# Benjamino.net
KiCad netlist of a schematic drawn in EAGLE
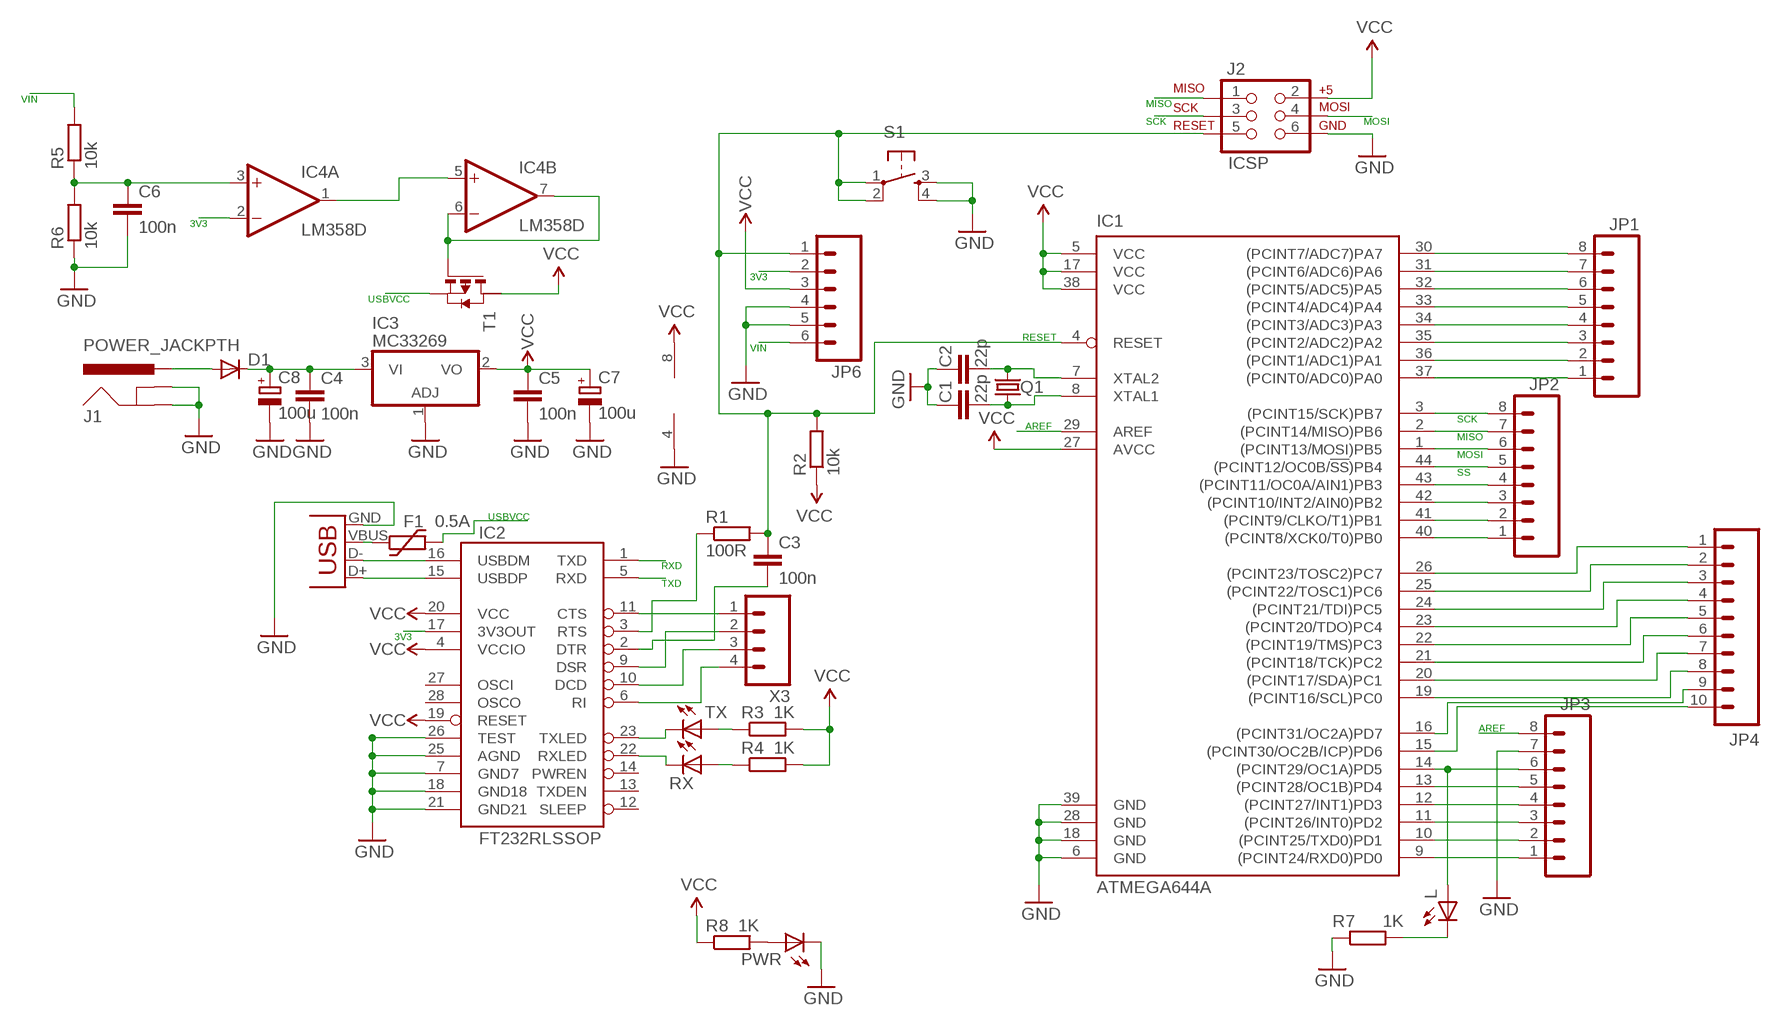
[diagram p0: schematic, sheet 1]

(export (version "E")
  (design (tool "Eeschema 10.0.6"))
  (components
    (comp (ref "C1")
      (value "22p")
      (footprint "eagle-import:C1206")
      (libsource (lib "eagle-import") (part "C-EUC1206"))
    )
    (comp (ref "C2")
      (value "22p")
      (footprint "eagle-import:C1206")
      (libsource (lib "eagle-import") (part "C-EUC1206"))
    )
    (comp (ref "C3")
      (value "100n")
      (footprint "eagle-import:C1206")
      (libsource (lib "eagle-import") (part "C-EUC1206"))
    )
    (comp (ref "C4")
      (value "100n")
      (footprint "eagle-import:C1206")
      (libsource (lib "eagle-import") (part "C-EUC1206"))
    )
    (comp (ref "C5")
      (value "100n")
      (footprint "eagle-import:C1206")
      (libsource (lib "eagle-import") (part "C-EUC1206"))
    )
    (comp (ref "C6")
      (value "100n")
      (footprint "eagle-import:C1206")
      (libsource (lib "eagle-import") (part "C-EUC1206"))
    )
    (comp (ref "C7")
      (value "100u")
      (footprint "eagle-import:PANASONIC_D")
      (libsource (lib "eagle-import") (part "CPOL-EUD"))
    )
    (comp (ref "C8")
      (value "100u")
      (footprint "eagle-import:PANASONIC_D")
      (libsource (lib "eagle-import") (part "CPOL-EUD"))
    )
    (comp (ref "D1")
      (value "DIODESMA")
      (footprint "eagle-import:SMA-DIODE")
      (libsource (lib "eagle-import") (part "DIODESMA"))
    )
    (comp (ref "F1")
      (value "0.5A")
      (footprint "eagle-import:1812L")
      (libsource (lib "eagle-import") (part "1812L"))
    )
    (comp (ref "IC1")
      (value "ATMEGA644A")
      (footprint "eagle-import:TQFP44")
      (fields (field (name "MPN") "ATMEGA644PV-10AU"))
      (libsource (lib "eagle-import") (part "ATMEGA644A"))
    )
    (comp (ref "IC2")
      (value "FT232RLSSOP")
      (footprint "eagle-import:SSOP28DB")
      (libsource (lib "eagle-import") (part "FT232RLSSOP"))
    )
    (comp (ref "IC3")
      (value "MC33269")
      (footprint "eagle-import:DPACK")
      (libsource (lib "eagle-import") (part "MC33269?D-5.0"))
    )
    (comp (ref "IC4")
      (value "LM358D")
      (footprint "eagle-import:SO08")
      (libsource (lib "eagle-import") (part "LM358D"))
    )
    (comp (ref "J1")
      (value "POWER_JACKPTH")
      (footprint "eagle-import:POWER_JACK_PTH")
      (libsource (lib "eagle-import") (part "POWER_JACKPTH"))
    )
    (comp (ref "J2")
      (value "ICSP")
      (footprint "eagle-import:2X3")
      (libsource (lib "eagle-import") (part "AVR_SPI_PRG_6PTH"))
    )
    (comp (ref "JP1")
      (value "M08")
      (footprint "eagle-import:1X08")
      (libsource (lib "eagle-import") (part "M08"))
    )
    (comp (ref "JP2")
      (value "M08")
      (footprint "eagle-import:1X08")
      (libsource (lib "eagle-import") (part "M08"))
    )
    (comp (ref "JP3")
      (value "M08")
      (footprint "eagle-import:1X08")
      (libsource (lib "eagle-import") (part "M08"))
    )
    (comp (ref "JP4")
      (value "M10\"")
      (footprint "eagle-import:1X10")
      (libsource (lib "eagle-import") (part "M10{dblquote}"))
    )
    (comp (ref "JP6")
      (value "M06SIP")
      (footprint "eagle-import:1X06")
      (libsource (lib "eagle-import") (part "M06SIP"))
    )
    (comp (ref "L")
      (value "LED1206")
      (footprint "eagle-import:LED-1206")
      (libsource (lib "eagle-import") (part "LED1206"))
    )
    (comp (ref "PWR")
      (value "LED1206")
      (footprint "eagle-import:LED-1206")
      (libsource (lib "eagle-import") (part "LED1206"))
    )
    (comp (ref "Q1")
      (value "CRYSTALHC49U-V")
      (footprint "eagle-import:HC49U-V")
      (libsource (lib "eagle-import") (part "CRYSTALHC49U-V"))
    )
    (comp (ref "R1")
      (value "100R")
      (footprint "eagle-import:R1206")
      (libsource (lib "eagle-import") (part "resistor_R-EU_R1206"))
    )
    (comp (ref "R2")
      (value "10k")
      (footprint "eagle-import:R1206")
      (libsource (lib "eagle-import") (part "R-EU_R1206"))
    )
    (comp (ref "R3")
      (value "1K")
      (footprint "eagle-import:R1206")
      (libsource (lib "eagle-import") (part "resistor_R-EU_R1206"))
    )
    (comp (ref "R4")
      (value "1K")
      (footprint "eagle-import:R1206")
      (libsource (lib "eagle-import") (part "resistor_R-EU_R1206"))
    )
    (comp (ref "R5")
      (value "10k")
      (footprint "eagle-import:R1206")
      (libsource (lib "eagle-import") (part "R-EU_R1206"))
    )
    (comp (ref "R6")
      (value "10k")
      (footprint "eagle-import:R1206")
      (libsource (lib "eagle-import") (part "R-EU_R1206"))
    )
    (comp (ref "R7")
      (value "1K")
      (footprint "eagle-import:R1206")
      (libsource (lib "eagle-import") (part "resistor_R-EU_R1206"))
    )
    (comp (ref "R8")
      (value "1K")
      (footprint "eagle-import:R1206")
      (libsource (lib "eagle-import") (part "resistor_R-EU_R1206"))
    )
    (comp (ref "RX")
      (value "LED1206")
      (footprint "eagle-import:LED-1206")
      (libsource (lib "eagle-import") (part "LED1206"))
    )
    (comp (ref "S1")
      (value "TAC_SWITCHPTH")
      (footprint "eagle-import:TACTILE-PTH")
      (libsource (lib "eagle-import") (part "TAC_SWITCHPTH"))
    )
    (comp (ref "T1")
      (value "PMOSSOT223")
      (footprint "eagle-import:SOT223")
      (libsource (lib "eagle-import") (part "PMOSSOT223"))
    )
    (comp (ref "TX")
      (value "LED1206")
      (footprint "eagle-import:LED-1206")
      (libsource (lib "eagle-import") (part "LED1206"))
    )
    (comp (ref "X1")
      (value "USBSMD")
      (footprint "eagle-import:USB-MINIB")
      (libsource (lib "eagle-import") (part "USBSMD"))
    )
    (comp (ref "X3")
      (value "M04PTH")
      (footprint "eagle-import:1X04")
      (libsource (lib "eagle-import") (part "M04PTH"))
    )
  )
  (nets
    (net (code "1") (name "/3V3") (class "Default")
      (node (ref "IC2") (pin "17") (pinfunction "3V3OUT_17") (pintype "output"))
      (node (ref "IC4") (pin "2") (pinfunction "-IN_2") (pintype "input"))
      (node (ref "JP6") (pin "2") (pinfunction "2_2") (pintype "passive"))
    )
    (net (code "2") (name "/AREF") (class "Default")
      (node (ref "IC1") (pin "29") (pinfunction "AREF_29") (pintype "passive"))
      (node (ref "JP3") (pin "8") (pinfunction "8_8") (pintype "passive"))
    )
    (net (code "3") (name "/MISO") (class "Default")
      (node (ref "IC1") (pin "2") (pinfunction "(PCINT14/MISO)PB6_2") (pintype "bidirectional"))
      (node (ref "J2") (pin "1") (pinfunction "1_1") (pintype "passive"))
      (node (ref "JP2") (pin "7") (pinfunction "7_7") (pintype "passive"))
    )
    (net (code "4") (name "/MOSI") (class "Default")
      (node (ref "IC1") (pin "1") (pinfunction "(PCINT13/MOSI)PB5_1") (pintype "bidirectional"))
      (node (ref "J2") (pin "4") (pinfunction "4_4") (pintype "passive"))
      (node (ref "JP2") (pin "6") (pinfunction "6_6") (pintype "passive"))
    )
    (net (code "5") (name "/RXD") (class "Default")
      (node (ref "IC1") (pin "9") (pinfunction "(PCINT24/RXD0)PD0_9") (pintype "bidirectional"))
      (node (ref "IC2") (pin "1") (pinfunction "TXD_1") (pintype "output"))
      (node (ref "JP3") (pin "1") (pinfunction "1_1") (pintype "passive"))
    )
    (net (code "6") (name "/SCK") (class "Default")
      (node (ref "IC1") (pin "3") (pinfunction "(PCINT15/SCK)PB7_3") (pintype "bidirectional"))
      (node (ref "J2") (pin "3") (pinfunction "3_3") (pintype "passive"))
      (node (ref "JP2") (pin "8") (pinfunction "8_8") (pintype "passive"))
    )
    (net (code "7") (name "/TXD") (class "Default")
      (node (ref "IC1") (pin "10") (pinfunction "(PCINT25/TXD0)PD1_10") (pintype "bidirectional"))
      (node (ref "IC2") (pin "5") (pinfunction "RXD_5") (pintype "input"))
      (node (ref "JP3") (pin "2") (pinfunction "2_2") (pintype "passive"))
    )
    (net (code "8") (name "/USBVCC") (class "Default")
      (node (ref "F1") (pin "P$2") (pinfunction "2_P$2") (pintype "passive"))
      (node (ref "T1") (pin "3") (pinfunction "S_3") (pintype "passive"))
    )
    (net (code "9") (name "/VIN") (class "Default")
      (node (ref "C4") (pin "1") (pinfunction "1_1") (pintype "passive"))
      (node (ref "C8") (pin "+") (pinfunction "+_+") (pintype "passive"))
      (node (ref "D1") (pin "C") (pinfunction "C_C") (pintype "passive"))
      (node (ref "IC3") (pin "3") (pinfunction "VI_3") (pintype "input"))
      (node (ref "JP6") (pin "6") (pinfunction "6_6") (pintype "passive"))
      (node (ref "R5") (pin "2") (pinfunction "2_2") (pintype "passive"))
    )
    (net (code "10") (name "GND") (class "Default")
      (node (ref "C1") (pin "1") (pinfunction "1_1") (pintype "passive"))
      (node (ref "C2") (pin "1") (pinfunction "1_1") (pintype "passive"))
      (node (ref "C4") (pin "2") (pinfunction "2_2") (pintype "passive"))
      (node (ref "C5") (pin "2") (pinfunction "2_2") (pintype "passive"))
      (node (ref "C6") (pin "2") (pinfunction "2_2") (pintype "passive"))
      (node (ref "C7") (pin "-") (pinfunction "-_-") (pintype "passive"))
      (node (ref "C8") (pin "-") (pinfunction "-_-") (pintype "passive"))
      (node (ref "IC1") (pin "18") (pinfunction "GND_18") (pintype "power_in"))
      (node (ref "IC1") (pin "28") (pinfunction "GND_28") (pintype "power_in"))
      (node (ref "IC1") (pin "39") (pinfunction "GND_39") (pintype "power_in"))
      (node (ref "IC1") (pin "6") (pinfunction "GND_6") (pintype "power_in"))
      (node (ref "IC2") (pin "18") (pinfunction "GND18_18") (pintype "power_in"))
      (node (ref "IC2") (pin "21") (pinfunction "GND21_21") (pintype "power_in"))
      (node (ref "IC2") (pin "25") (pinfunction "AGND_25") (pintype "power_in"))
      (node (ref "IC2") (pin "26") (pinfunction "TEST_26") (pintype "input"))
      (node (ref "IC2") (pin "7") (pinfunction "GND7_7") (pintype "power_in"))
      (node (ref "IC3") (pin "1") (pinfunction "ADJ_1") (pintype "input"))
      (node (ref "IC4") (pin "4") (pinfunction "V-_4") (pintype "power_in"))
      (node (ref "J1") (pin "GND") (pinfunction "GND_GND") (pintype "bidirectional"))
      (node (ref "J1") (pin "GNDBREAK") (pinfunction "GNDBREAK_GNDBREAK") (pintype "bidirectional"))
      (node (ref "J2") (pin "6") (pinfunction "6_6") (pintype "passive"))
      (node (ref "JP3") (pin "7") (pinfunction "7_7") (pintype "passive"))
      (node (ref "JP6") (pin "4") (pinfunction "4_4") (pintype "passive"))
      (node (ref "JP6") (pin "5") (pinfunction "5_5") (pintype "passive"))
      (node (ref "PWR") (pin "C") (pinfunction "C_C") (pintype "passive"))
      (node (ref "R6") (pin "1") (pinfunction "1_1") (pintype "passive"))
      (node (ref "R7") (pin "1") (pinfunction "1_1") (pintype "passive"))
      (node (ref "S1") (pin "3") (pinfunction "3_3") (pintype "passive"))
      (node (ref "S1") (pin "4") (pinfunction "4_4") (pintype "passive"))
      (node (ref "X1") (pin "GND") (pinfunction "GND_GND") (pintype "bidirectional"))
    )
    (net (code "11") (name "Net-(D1-PadA)") (class "Default")
      (node (ref "D1") (pin "A") (pinfunction "A_A") (pintype "passive"))
      (node (ref "J1") (pin "PWR") (pinfunction "PWR_PWR") (pintype "bidirectional"))
    )
    (net (code "12") (name "Net-(F1-1)") (class "Default")
      (node (ref "F1") (pin "P$1") (pinfunction "1_P$1") (pintype "passive"))
      (node (ref "X1") (pin "VBUS") (pinfunction "VBUS_VBUS") (pintype "bidirectional"))
    )
    (net (code "13") (name "Net-(IC1-(PCINT0{slash}ADC0)PA0)") (class "Default")
      (node (ref "IC1") (pin "37") (pinfunction "(PCINT0/ADC0)PA0_37") (pintype "bidirectional"))
      (node (ref "JP1") (pin "1") (pinfunction "1_1") (pintype "passive"))
    )
    (net (code "14") (name "Net-(IC1-(PCINT1{slash}ADC1)PA1)") (class "Default")
      (node (ref "IC1") (pin "36") (pinfunction "(PCINT1/ADC1)PA1_36") (pintype "bidirectional"))
      (node (ref "JP1") (pin "2") (pinfunction "2_2") (pintype "passive"))
    )
    (net (code "15") (name "Net-(IC1-(PCINT2{slash}ADC2)PA2)") (class "Default")
      (node (ref "IC1") (pin "35") (pinfunction "(PCINT2/ADC2)PA2_35") (pintype "bidirectional"))
      (node (ref "JP1") (pin "3") (pinfunction "3_3") (pintype "passive"))
    )
    (net (code "16") (name "Net-(IC1-(PCINT3{slash}ADC3)PA3)") (class "Default")
      (node (ref "IC1") (pin "34") (pinfunction "(PCINT3/ADC3)PA3_34") (pintype "bidirectional"))
      (node (ref "JP1") (pin "4") (pinfunction "4_4") (pintype "passive"))
    )
    (net (code "17") (name "Net-(IC1-(PCINT4{slash}ADC4)PA4)") (class "Default")
      (node (ref "IC1") (pin "33") (pinfunction "(PCINT4/ADC4)PA4_33") (pintype "bidirectional"))
      (node (ref "JP1") (pin "5") (pinfunction "5_5") (pintype "passive"))
    )
    (net (code "18") (name "Net-(IC1-(PCINT5{slash}ADC5)PA5)") (class "Default")
      (node (ref "IC1") (pin "32") (pinfunction "(PCINT5/ADC5)PA5_32") (pintype "bidirectional"))
      (node (ref "JP1") (pin "6") (pinfunction "6_6") (pintype "passive"))
    )
    (net (code "19") (name "Net-(IC1-(PCINT6{slash}ADC6)PA6)") (class "Default")
      (node (ref "IC1") (pin "31") (pinfunction "(PCINT6/ADC6)PA6_31") (pintype "bidirectional"))
      (node (ref "JP1") (pin "7") (pinfunction "7_7") (pintype "passive"))
    )
    (net (code "20") (name "Net-(IC1-(PCINT7{slash}ADC7)PA7)") (class "Default")
      (node (ref "IC1") (pin "30") (pinfunction "(PCINT7/ADC7)PA7_30") (pintype "bidirectional"))
      (node (ref "JP1") (pin "8") (pinfunction "8_8") (pintype "passive"))
    )
    (net (code "21") (name "Net-(IC1-(PCINT8{slash}XCK0{slash}T0)PB0)") (class "Default")
      (node (ref "IC1") (pin "40") (pinfunction "(PCINT8/XCK0/T0)PB0_40") (pintype "bidirectional"))
      (node (ref "JP2") (pin "1") (pinfunction "1_1") (pintype "passive"))
    )
    (net (code "22") (name "Net-(IC1-(PCINT9{slash}CLKO{slash}T1)PB1)") (class "Default")
      (node (ref "IC1") (pin "41") (pinfunction "(PCINT9/CLKO/T1)PB1_41") (pintype "bidirectional"))
      (node (ref "JP2") (pin "2") (pinfunction "2_2") (pintype "passive"))
    )
    (net (code "23") (name "Net-(IC1-(PCINT10{slash}INT2{slash}AIN0)PB2)") (class "Default")
      (node (ref "IC1") (pin "42") (pinfunction "(PCINT10/INT2/AIN0)PB2_42") (pintype "bidirectional"))
      (node (ref "JP2") (pin "3") (pinfunction "3_3") (pintype "passive"))
    )
    (net (code "24") (name "Net-(IC1-(PCINT11{slash}OC0A{slash}AIN1)PB3)") (class "Default")
      (node (ref "IC1") (pin "43") (pinfunction "(PCINT11/OC0A/AIN1)PB3_43") (pintype "bidirectional"))
      (node (ref "JP2") (pin "4") (pinfunction "4_4") (pintype "passive"))
    )
    (net (code "25") (name "Net-(IC1-(PCINT12{slash}OC0B{slash}~{SS})PB4)") (class "Default")
      (node (ref "IC1") (pin "44") (pinfunction "(PCINT12/OC0B/~{SS})PB4_44") (pintype "bidirectional"))
      (node (ref "JP2") (pin "5") (pinfunction "5_5") (pintype "passive"))
    )
    (net (code "26") (name "Net-(IC1-(PCINT16{slash}SCL)PC0)") (class "Default")
      (node (ref "IC1") (pin "19") (pinfunction "(PCINT16/SCL)PC0_19") (pintype "output"))
      (node (ref "JP4") (pin "8") (pinfunction "8_8") (pintype "passive"))
    )
    (net (code "27") (name "Net-(IC1-(PCINT17{slash}SDA)PC1)") (class "Default")
      (node (ref "IC1") (pin "20") (pinfunction "(PCINT17/SDA)PC1_20") (pintype "output"))
      (node (ref "JP4") (pin "7") (pinfunction "7_7") (pintype "passive"))
    )
    (net (code "28") (name "Net-(IC1-(PCINT18{slash}TCK)PC2)") (class "Default")
      (node (ref "IC1") (pin "21") (pinfunction "(PCINT18/TCK)PC2_21") (pintype "output"))
      (node (ref "JP4") (pin "6") (pinfunction "6_6") (pintype "passive"))
    )
    (net (code "29") (name "Net-(IC1-(PCINT19{slash}TMS)PC3)") (class "Default")
      (node (ref "IC1") (pin "22") (pinfunction "(PCINT19/TMS)PC3_22") (pintype "output"))
      (node (ref "JP4") (pin "5") (pinfunction "5_5") (pintype "passive"))
    )
    (net (code "30") (name "Net-(IC1-(PCINT20{slash}TDO)PC4)") (class "Default")
      (node (ref "IC1") (pin "23") (pinfunction "(PCINT20/TDO)PC4_23") (pintype "output"))
      (node (ref "JP4") (pin "4") (pinfunction "4_4") (pintype "passive"))
    )
    (net (code "31") (name "Net-(IC1-(PCINT21{slash}TDI)PC5)") (class "Default")
      (node (ref "IC1") (pin "24") (pinfunction "(PCINT21/TDI)PC5_24") (pintype "output"))
      (node (ref "JP4") (pin "3") (pinfunction "3_3") (pintype "passive"))
    )
    (net (code "32") (name "Net-(IC1-(PCINT22{slash}TOSC1)PC6)") (class "Default")
      (node (ref "IC1") (pin "25") (pinfunction "(PCINT22/TOSC1)PC6_25") (pintype "output"))
      (node (ref "JP4") (pin "2") (pinfunction "2_2") (pintype "passive"))
    )
    (net (code "33") (name "Net-(IC1-(PCINT23{slash}TOSC2)PC7)") (class "Default")
      (node (ref "IC1") (pin "26") (pinfunction "(PCINT23/TOSC2)PC7_26") (pintype "output"))
      (node (ref "JP4") (pin "1") (pinfunction "1_1") (pintype "passive"))
    )
    (net (code "34") (name "Net-(IC1-(PCINT26{slash}INT0)PD2)") (class "Default")
      (node (ref "IC1") (pin "11") (pinfunction "(PCINT26/INT0)PD2_11") (pintype "bidirectional"))
      (node (ref "JP3") (pin "3") (pinfunction "3_3") (pintype "passive"))
    )
    (net (code "35") (name "Net-(IC1-(PCINT27{slash}INT1)PD3)") (class "Default")
      (node (ref "IC1") (pin "12") (pinfunction "(PCINT27/INT1)PD3_12") (pintype "bidirectional"))
      (node (ref "JP3") (pin "4") (pinfunction "4_4") (pintype "passive"))
    )
    (net (code "36") (name "Net-(IC1-(PCINT28{slash}OC1B)PD4)") (class "Default")
      (node (ref "IC1") (pin "13") (pinfunction "(PCINT28/OC1B)PD4_13") (pintype "bidirectional"))
      (node (ref "JP3") (pin "5") (pinfunction "5_5") (pintype "passive"))
    )
    (net (code "37") (name "Net-(IC1-(PCINT29{slash}OC1A)PD5)") (class "Default")
      (node (ref "IC1") (pin "14") (pinfunction "(PCINT29/OC1A)PD5_14") (pintype "bidirectional"))
      (node (ref "JP3") (pin "6") (pinfunction "6_6") (pintype "passive"))
      (node (ref "L") (pin "A") (pinfunction "A_A") (pintype "passive"))
    )
    (net (code "38") (name "Net-(IC1-(PCINT30{slash}OC2B{slash}ICP)PD6)") (class "Default")
      (node (ref "IC1") (pin "15") (pinfunction "(PCINT30/OC2B/ICP)PD6_15") (pintype "bidirectional"))
      (node (ref "JP4") (pin "10") (pinfunction "10_10") (pintype "passive"))
    )
    (net (code "39") (name "Net-(IC1-(PCINT31{slash}OC2A)PD7)") (class "Default")
      (node (ref "IC1") (pin "16") (pinfunction "(PCINT31/OC2A)PD7_16") (pintype "bidirectional"))
      (node (ref "JP4") (pin "9") (pinfunction "9_9") (pintype "passive"))
    )
    (net (code "40") (name "Net-(IC1-RESET)") (class "Default")
      (node (ref "C3") (pin "1") (pinfunction "1_1") (pintype "passive"))
      (node (ref "IC1") (pin "4") (pinfunction "RESET_4") (pintype "input"))
      (node (ref "J2") (pin "5") (pinfunction "5_5") (pintype "passive"))
      (node (ref "JP6") (pin "1") (pinfunction "1_1") (pintype "passive"))
      (node (ref "R1") (pin "2") (pinfunction "2_2") (pintype "passive"))
      (node (ref "R2") (pin "2") (pinfunction "2_2") (pintype "passive"))
      (node (ref "S1") (pin "1") (pinfunction "1_1") (pintype "passive"))
      (node (ref "S1") (pin "2") (pinfunction "2_2") (pintype "passive"))
    )
    (net (code "41") (name "Net-(IC1-XTAL1)") (class "Default")
      (node (ref "C1") (pin "2") (pinfunction "2_2") (pintype "passive"))
      (node (ref "IC1") (pin "8") (pinfunction "XTAL1_8") (pintype "bidirectional"))
      (node (ref "Q1") (pin "1") (pinfunction "1_1") (pintype "passive"))
    )
    (net (code "42") (name "Net-(IC1-XTAL2)") (class "Default")
      (node (ref "C2") (pin "2") (pinfunction "2_2") (pintype "passive"))
      (node (ref "IC1") (pin "7") (pinfunction "XTAL2_7") (pintype "bidirectional"))
      (node (ref "Q1") (pin "2") (pinfunction "2_2") (pintype "passive"))
    )
    (net (code "43") (name "Net-(IC2-CTS)") (class "Default")
      (node (ref "IC2") (pin "11") (pinfunction "CTS_11") (pintype "input"))
      (node (ref "X3") (pin "1") (pinfunction "1_1") (pintype "passive"))
    )
    (net (code "44") (name "Net-(IC2-DCD)") (class "Default")
      (node (ref "IC2") (pin "10") (pinfunction "DCD_10") (pintype "input"))
      (node (ref "X3") (pin "3") (pinfunction "3_3") (pintype "passive"))
    )
    (net (code "45") (name "Net-(IC2-DSR)") (class "Default")
      (node (ref "IC2") (pin "9") (pinfunction "DSR_9") (pintype "input"))
      (node (ref "X3") (pin "2") (pinfunction "2_2") (pintype "passive"))
    )
    (net (code "46") (name "Net-(IC2-DTR)") (class "Default")
      (node (ref "C3") (pin "2") (pinfunction "2_2") (pintype "passive"))
      (node (ref "IC2") (pin "2") (pinfunction "DTR_2") (pintype "output"))
    )
    (net (code "47") (name "Net-(IC2-RI)") (class "Default")
      (node (ref "IC2") (pin "6") (pinfunction "RI_6") (pintype "input"))
      (node (ref "X3") (pin "4") (pinfunction "4_4") (pintype "passive"))
    )
    (net (code "48") (name "Net-(IC2-RTS)") (class "Default")
      (node (ref "IC2") (pin "3") (pinfunction "RTS_3") (pintype "output"))
      (node (ref "R1") (pin "1") (pinfunction "1_1") (pintype "passive"))
    )
    (net (code "49") (name "Net-(IC2-RXLED)") (class "Default")
      (node (ref "IC2") (pin "22") (pinfunction "RXLED_22") (pintype "input"))
      (node (ref "RX") (pin "C") (pinfunction "C_C") (pintype "passive"))
    )
    (net (code "50") (name "Net-(IC2-TXLED)") (class "Default")
      (node (ref "IC2") (pin "23") (pinfunction "TXLED_23") (pintype "input"))
      (node (ref "TX") (pin "C") (pinfunction "C_C") (pintype "passive"))
    )
    (net (code "51") (name "Net-(IC2-USBDM)") (class "Default")
      (node (ref "IC2") (pin "16") (pinfunction "USBDM_16") (pintype "bidirectional"))
      (node (ref "X1") (pin "D-") (pinfunction "D-_D-") (pintype "bidirectional"))
    )
    (net (code "52") (name "Net-(IC2-USBDP)") (class "Default")
      (node (ref "IC2") (pin "15") (pinfunction "USBDP_15") (pintype "bidirectional"))
      (node (ref "X1") (pin "D+") (pinfunction "D+_D+") (pintype "bidirectional"))
    )
    (net (code "53") (name "Net-(IC4A-+IN)") (class "Default")
      (node (ref "C6") (pin "1") (pinfunction "1_1") (pintype "passive"))
      (node (ref "IC4") (pin "3") (pinfunction "+IN_3") (pintype "input"))
      (node (ref "R5") (pin "1") (pinfunction "1_1") (pintype "passive"))
      (node (ref "R6") (pin "2") (pinfunction "2_2") (pintype "passive"))
    )
    (net (code "54") (name "Net-(IC4A-OUT)") (class "Default")
      (node (ref "IC4") (pin "1") (pinfunction "OUT_1") (pintype "output"))
      (node (ref "IC4") (pin "5") (pinfunction "+IN_5") (pintype "input"))
    )
    (net (code "55") (name "Net-(IC4B--IN)") (class "Default")
      (node (ref "IC4") (pin "6") (pinfunction "-IN_6") (pintype "input"))
      (node (ref "IC4") (pin "7") (pinfunction "OUT_7") (pintype "output"))
      (node (ref "T1") (pin "1") (pinfunction "G_1") (pintype "passive"))
    )
    (net (code "56") (name "Net-(L-PadC)") (class "Default")
      (node (ref "L") (pin "C") (pinfunction "C_C") (pintype "passive"))
      (node (ref "R7") (pin "2") (pinfunction "2_2") (pintype "passive"))
    )
    (net (code "57") (name "Net-(PWR-PadA)") (class "Default")
      (node (ref "PWR") (pin "A") (pinfunction "A_A") (pintype "passive"))
      (node (ref "R8") (pin "2") (pinfunction "2_2") (pintype "passive"))
    )
    (net (code "58") (name "Net-(R3-Pad1)") (class "Default")
      (node (ref "R3") (pin "1") (pinfunction "1_1") (pintype "passive"))
      (node (ref "TX") (pin "A") (pinfunction "A_A") (pintype "passive"))
    )
    (net (code "59") (name "Net-(R4-Pad1)") (class "Default")
      (node (ref "R4") (pin "1") (pinfunction "1_1") (pintype "passive"))
      (node (ref "RX") (pin "A") (pinfunction "A_A") (pintype "passive"))
    )
    (net (code "60") (name "VCC") (class "Default")
      (node (ref "C5") (pin "1") (pinfunction "1_1") (pintype "passive"))
      (node (ref "C7") (pin "+") (pinfunction "+_+") (pintype "passive"))
      (node (ref "IC1") (pin "17") (pinfunction "VCC_17") (pintype "power_in"))
      (node (ref "IC1") (pin "27") (pinfunction "AVCC_27") (pintype "power_in"))
      (node (ref "IC1") (pin "38") (pinfunction "VCC_38") (pintype "power_in"))
      (node (ref "IC1") (pin "5") (pinfunction "VCC_5") (pintype "power_in"))
      (node (ref "IC2") (pin "19") (pinfunction "RESET_19") (pintype "input"))
      (node (ref "IC2") (pin "20") (pinfunction "VCC_20") (pintype "power_in"))
      (node (ref "IC2") (pin "4") (pinfunction "VCCIO_4") (pintype "power_in"))
      (node (ref "IC3") (pin "2") (pinfunction "VO_2") (pintype "passive"))
      (node (ref "IC4") (pin "8") (pinfunction "V+_8") (pintype "power_in"))
      (node (ref "J2") (pin "2") (pinfunction "2_2") (pintype "passive"))
      (node (ref "JP6") (pin "3") (pinfunction "3_3") (pintype "passive"))
      (node (ref "R2") (pin "1") (pinfunction "1_1") (pintype "passive"))
      (node (ref "R3") (pin "2") (pinfunction "2_2") (pintype "passive"))
      (node (ref "R4") (pin "2") (pinfunction "2_2") (pintype "passive"))
      (node (ref "R8") (pin "1") (pinfunction "1_1") (pintype "passive"))
      (node (ref "T1") (pin "2") (pinfunction "D_2") (pintype "passive"))
    )
    (net (code "61") (name "unconnected-(IC2-OSCI-Pad27)") (class "Default")
      (node (ref "IC2") (pin "27") (pinfunction "OSCI_27") (pintype "input"))
    )
    (net (code "62") (name "unconnected-(IC2-OSCO-Pad28)") (class "Default")
      (node (ref "IC2") (pin "28") (pinfunction "OSCO_28") (pintype "output"))
    )
    (net (code "63") (name "unconnected-(IC2-PWREN-Pad14)") (class "Default")
      (node (ref "IC2") (pin "14") (pinfunction "PWREN_14") (pintype "input"))
    )
    (net (code "64") (name "unconnected-(IC2-SLEEP-Pad12)") (class "Default")
      (node (ref "IC2") (pin "12") (pinfunction "SLEEP_12") (pintype "input"))
    )
    (net (code "65") (name "unconnected-(IC2-TXDEN-Pad13)") (class "Default")
      (node (ref "IC2") (pin "13") (pinfunction "TXDEN_13") (pintype "input"))
    )
    (net (code "66") (name "unconnected-(T1-D2-Pad4)") (class "Default")
      (node (ref "T1") (pin "4") (pinfunction "D2_4") (pintype "passive"))
    )
  )
)
